# STM32_microcontroller_power.net
KiCad netlist of a schematic drawn in Altium Designer
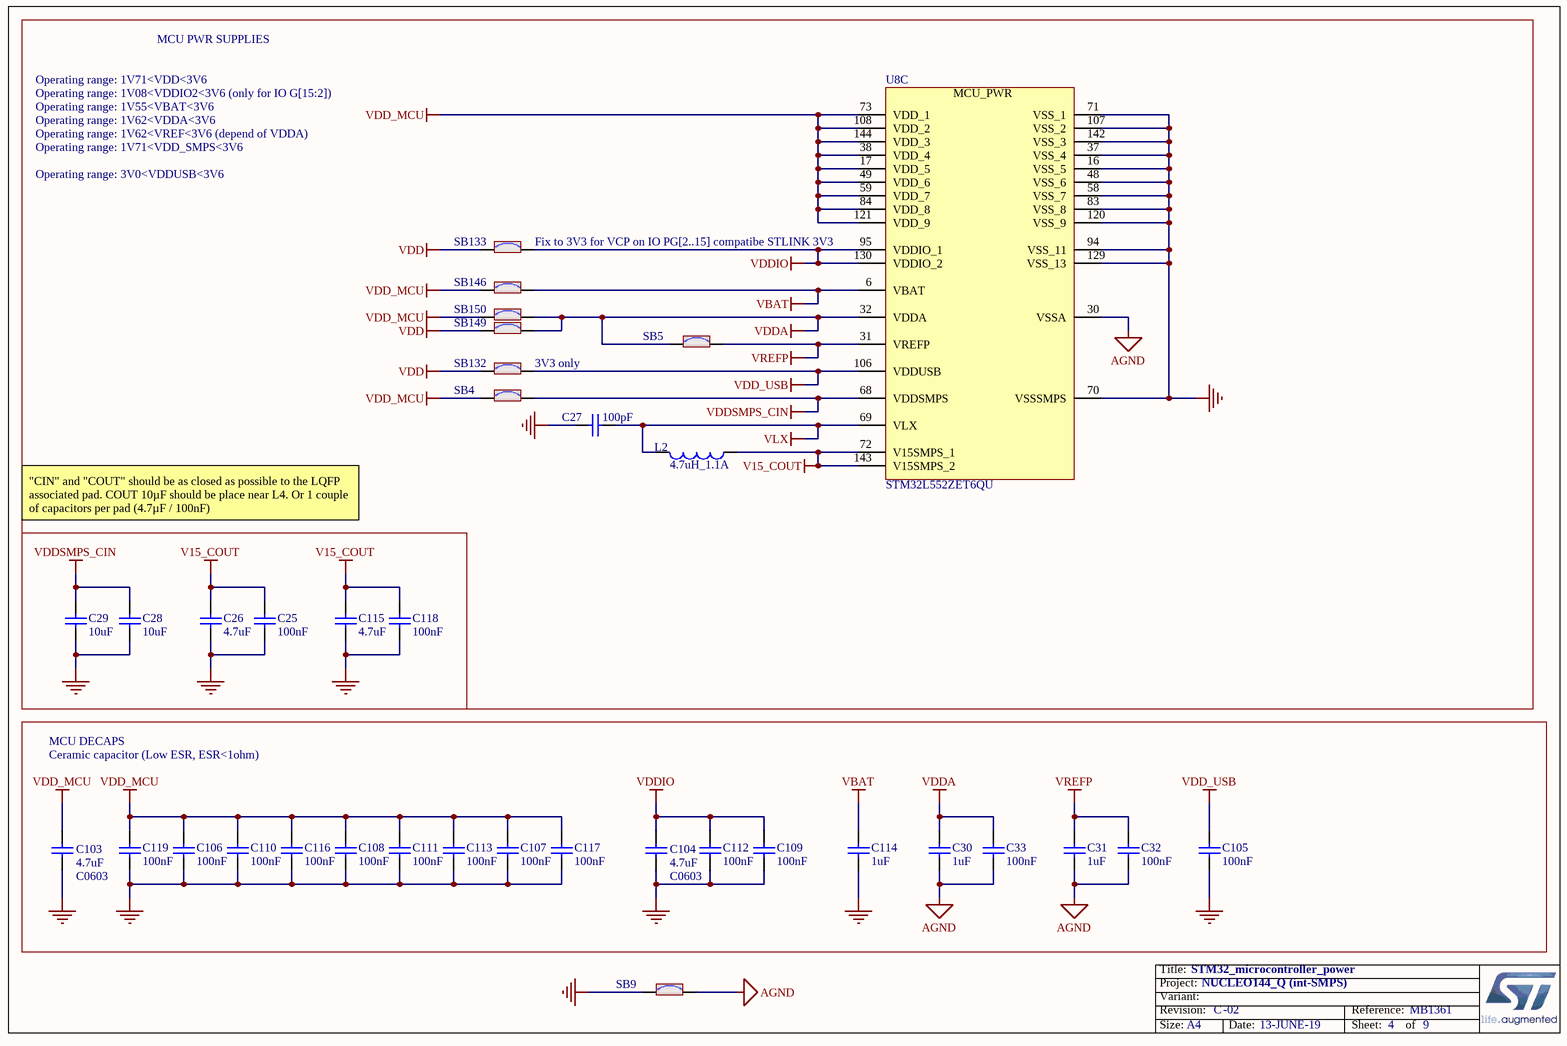
[diagram p0: STM32_microcontroller_power.SchDoc]

(export (version "E")
  (design (tool "Eeschema 10.0.6"))
  (components
    (comp (ref "C25")
      (value "100nF")
      (footprint "C0402")
      (description "Capacitor, MLCC, 100nF, 16V, X7R, 10%, 0402, T=0,5mm")
      (fields
        (field (name "INTERNAL_PART_NUMBER") "MCD-00102")
        (field (name "MANUFACTURER_PART_NUMBER") "CC0402KRX7R7BB104")
        (field (name "PROVIDED_BY") "SUBCO")
      )
      (libsource (lib "MCD_PARTS_database") (part "Capacitor"))
    )
    (comp (ref "C26")
      (value "4.7uF")
      (footprint "C0402")
      (description "Capacitor, MLCC, 4.7uF, 6V3, X5R, 20%, 0402, T=0,5mm")
      (fields
        (field (name "INTERNAL_PART_NUMBER") "MCD-01356")
        (field (name "MANUFACTURER_PART_NUMBER") "GRM155R60J475ME47")
        (field (name "PROVIDED_BY") "Subcon")
      )
      (libsource (lib "MCD_PARTS_database") (part "Capacitor"))
    )
    (comp (ref "C27")
      (value "100pF")
      (footprint "C0402")
      (description "Capacitor, MLCC, 100pF, 50V, NPO, 5%, 0402, T=0,5mm")
      (fields
        (field (name "INTERNAL_PART_NUMBER") "MCD-00205")
        (field (name "MANUFACTURER_PART_NUMBER") "CC0402JRNPO9BN101")
        (field (name "PROVIDED_BY") "Subcon")
      )
      (libsource (lib "MCD_PARTS_database") (part "Capacitor"))
    )
    (comp (ref "C28")
      (value "10uF")
      (footprint "C0402")
      (description "Capacitor, MLCC, 10uF, 4V, X5R, 20%, 0402, T=0,5mm")
      (fields
        (field (name "INTERNAL_PART_NUMBER") "MCD-01355")
        (field (name "MANUFACTURER_PART_NUMBER") "GRM155R60G106ME44")
        (field (name "PROVIDED_BY") "Subcon")
      )
      (libsource (lib "MCD_PARTS_database") (part "Capacitor"))
    )
    (comp (ref "C29")
      (value "10uF")
      (footprint "C0402")
      (description "Capacitor, MLCC, 10uF, 4V, X5R, 20%, 0402, T=0,5mm")
      (fields
        (field (name "INTERNAL_PART_NUMBER") "MCD-01355")
        (field (name "MANUFACTURER_PART_NUMBER") "GRM155R60G106ME44")
        (field (name "PROVIDED_BY") "Subcon")
      )
      (libsource (lib "MCD_PARTS_database") (part "Capacitor"))
    )
    (comp (ref "C30")
      (value "1uF")
      (footprint "C0603")
      (description "Capacitor, MLCC, 1uF, 16V, X5R, 10%, 0603, T=0,8mm")
      (fields
        (field (name "INTERNAL_PART_NUMBER") "MCD-00010")
        (field (name "MANUFACTURER_PART_NUMBER") "CC0603KRX5R7BB105")
        (field (name "PROVIDED_BY") "SUBCO")
      )
      (libsource (lib "MCD_PARTS_database") (part "Capacitor"))
    )
    (comp (ref "C31")
      (value "1uF")
      (footprint "C0603")
      (description "Capacitor, MLCC, 1uF, 16V, X5R, 10%, 0603, T=0,8mm")
      (fields
        (field (name "INTERNAL_PART_NUMBER") "MCD-00010")
        (field (name "MANUFACTURER_PART_NUMBER") "CC0603KRX5R7BB105")
        (field (name "PROVIDED_BY") "SUBCO")
      )
      (libsource (lib "MCD_PARTS_database") (part "Capacitor"))
    )
    (comp (ref "C32")
      (value "100nF")
      (footprint "C0402")
      (description "Capacitor, MLCC, 100nF, 16V, X7R, 10%, 0402, T=0,5mm")
      (fields
        (field (name "INTERNAL_PART_NUMBER") "MCD-00102")
        (field (name "MANUFACTURER_PART_NUMBER") "CC0402KRX7R7BB104")
        (field (name "PROVIDED_BY") "SUBCO")
      )
      (libsource (lib "MCD_PARTS_database") (part "Capacitor"))
    )
    (comp (ref "C33")
      (value "100nF")
      (footprint "C0402")
      (description "Capacitor, MLCC, 100nF, 16V, X7R, 10%, 0402, T=0,5mm")
      (fields
        (field (name "INTERNAL_PART_NUMBER") "MCD-00102")
        (field (name "MANUFACTURER_PART_NUMBER") "CC0402KRX7R7BB104")
        (field (name "PROVIDED_BY") "SUBCO")
      )
      (libsource (lib "MCD_PARTS_database") (part "Capacitor"))
    )
    (comp (ref "C103")
      (value "4.7uF")
      (footprint "C0603")
      (description "Capacitor, MLCC, 4.7µF, 10V, X5R, 20%, 0603, T=0,8mm")
      (fields
        (field (name "INTERNAL_PART_NUMBER") "MCD-01121")
        (field (name "MANUFACTURER_PART_NUMBER") "GRM188R61A475ME15")
        (field (name "PACKAGE") "C0603")
        (field (name "PROVIDED_BY") "Subcon")
      )
      (libsource (lib "MCD_PARTS_database") (part "Capacitor"))
    )
    (comp (ref "C104")
      (value "4.7uF")
      (footprint "C0603")
      (description "Capacitor, MLCC, 4.7µF, 10V, X5R, 20%, 0603, T=0,8mm")
      (fields
        (field (name "INTERNAL_PART_NUMBER") "MCD-01121")
        (field (name "MANUFACTURER_PART_NUMBER") "GRM188R61A475ME15")
        (field (name "PACKAGE") "C0603")
        (field (name "PROVIDED_BY") "Subcon")
      )
      (libsource (lib "MCD_PARTS_database") (part "Capacitor"))
    )
    (comp (ref "C105")
      (value "100nF")
      (footprint "C0402")
      (description "Capacitor, MLCC, 100nF, 16V, X7R, 10%, 0402, T=0,5mm")
      (fields
        (field (name "INTERNAL_PART_NUMBER") "MCD-00102")
        (field (name "MANUFACTURER_PART_NUMBER") "CC0402KRX7R7BB104")
        (field (name "PROVIDED_BY") "SUBCO")
      )
      (libsource (lib "MCD_PARTS_database") (part "Capacitor"))
    )
    (comp (ref "C106")
      (value "100nF")
      (footprint "C0402")
      (description "Capacitor, MLCC, 100nF, 16V, X7R, 10%, 0402, T=0,5mm")
      (fields
        (field (name "INTERNAL_PART_NUMBER") "MCD-00102")
        (field (name "MANUFACTURER_PART_NUMBER") "CC0402KRX7R7BB104")
        (field (name "PROVIDED_BY") "SUBCO")
      )
      (libsource (lib "MCD_PARTS_database") (part "Capacitor"))
    )
    (comp (ref "C107")
      (value "100nF")
      (footprint "C0402")
      (description "Capacitor, MLCC, 100nF, 16V, X7R, 10%, 0402, T=0,5mm")
      (fields
        (field (name "INTERNAL_PART_NUMBER") "MCD-00102")
        (field (name "MANUFACTURER_PART_NUMBER") "CC0402KRX7R7BB104")
        (field (name "PROVIDED_BY") "SUBCO")
      )
      (libsource (lib "MCD_PARTS_database") (part "Capacitor"))
    )
    (comp (ref "C108")
      (value "100nF")
      (footprint "C0402")
      (description "Capacitor, MLCC, 100nF, 16V, X7R, 10%, 0402, T=0,5mm")
      (fields
        (field (name "INTERNAL_PART_NUMBER") "MCD-00102")
        (field (name "MANUFACTURER_PART_NUMBER") "CC0402KRX7R7BB104")
        (field (name "PROVIDED_BY") "SUBCO")
      )
      (libsource (lib "MCD_PARTS_database") (part "Capacitor"))
    )
    (comp (ref "C109")
      (value "100nF")
      (footprint "C0402")
      (description "Capacitor, MLCC, 100nF, 16V, X7R, 10%, 0402, T=0,5mm")
      (fields
        (field (name "INTERNAL_PART_NUMBER") "MCD-00102")
        (field (name "MANUFACTURER_PART_NUMBER") "CC0402KRX7R7BB104")
        (field (name "PROVIDED_BY") "SUBCO")
      )
      (libsource (lib "MCD_PARTS_database") (part "Capacitor"))
    )
    (comp (ref "C110")
      (value "100nF")
      (footprint "C0402")
      (description "Capacitor, MLCC, 100nF, 16V, X7R, 10%, 0402, T=0,5mm")
      (fields
        (field (name "INTERNAL_PART_NUMBER") "MCD-00102")
        (field (name "MANUFACTURER_PART_NUMBER") "CC0402KRX7R7BB104")
        (field (name "PROVIDED_BY") "SUBCO")
      )
      (libsource (lib "MCD_PARTS_database") (part "Capacitor"))
    )
    (comp (ref "C111")
      (value "100nF")
      (footprint "C0402")
      (description "Capacitor, MLCC, 100nF, 16V, X7R, 10%, 0402, T=0,5mm")
      (fields
        (field (name "INTERNAL_PART_NUMBER") "MCD-00102")
        (field (name "MANUFACTURER_PART_NUMBER") "CC0402KRX7R7BB104")
        (field (name "PROVIDED_BY") "SUBCO")
      )
      (libsource (lib "MCD_PARTS_database") (part "Capacitor"))
    )
    (comp (ref "C112")
      (value "100nF")
      (footprint "C0402")
      (description "Capacitor, MLCC, 100nF, 16V, X7R, 10%, 0402, T=0,5mm")
      (fields
        (field (name "INTERNAL_PART_NUMBER") "MCD-00102")
        (field (name "MANUFACTURER_PART_NUMBER") "CC0402KRX7R7BB104")
        (field (name "PROVIDED_BY") "SUBCO")
      )
      (libsource (lib "MCD_PARTS_database") (part "Capacitor"))
    )
    (comp (ref "C113")
      (value "100nF")
      (footprint "C0402")
      (description "Capacitor, MLCC, 100nF, 16V, X7R, 10%, 0402, T=0,5mm")
      (fields
        (field (name "INTERNAL_PART_NUMBER") "MCD-00102")
        (field (name "MANUFACTURER_PART_NUMBER") "CC0402KRX7R7BB104")
        (field (name "PROVIDED_BY") "SUBCO")
      )
      (libsource (lib "MCD_PARTS_database") (part "Capacitor"))
    )
    (comp (ref "C114")
      (value "1uF")
      (footprint "C0603")
      (description "Capacitor, MLCC, 1uF, 16V, X5R, 10%, 0603, T=0,8mm")
      (fields
        (field (name "INTERNAL_PART_NUMBER") "MCD-00010")
        (field (name "MANUFACTURER_PART_NUMBER") "CC0603KRX5R7BB105")
        (field (name "PROVIDED_BY") "SUBCO")
      )
      (libsource (lib "MCD_PARTS_database") (part "Capacitor"))
    )
    (comp (ref "C115")
      (value "4.7uF")
      (footprint "C0402")
      (description "Capacitor, MLCC, 4.7uF, 6V3, X5R, 20%, 0402, T=0,5mm")
      (fields
        (field (name "INTERNAL_PART_NUMBER") "MCD-01356")
        (field (name "MANUFACTURER_PART_NUMBER") "GRM155R60J475ME47")
        (field (name "PROVIDED_BY") "Subcon")
      )
      (libsource (lib "MCD_PARTS_database") (part "Capacitor"))
    )
    (comp (ref "C116")
      (value "100nF")
      (footprint "C0402")
      (description "Capacitor, MLCC, 100nF, 16V, X7R, 10%, 0402, T=0,5mm")
      (fields
        (field (name "INTERNAL_PART_NUMBER") "MCD-00102")
        (field (name "MANUFACTURER_PART_NUMBER") "CC0402KRX7R7BB104")
        (field (name "PROVIDED_BY") "SUBCO")
      )
      (libsource (lib "MCD_PARTS_database") (part "Capacitor"))
    )
    (comp (ref "C117")
      (value "100nF")
      (footprint "C0402")
      (description "Capacitor, MLCC, 100nF, 16V, X7R, 10%, 0402, T=0,5mm")
      (fields
        (field (name "INTERNAL_PART_NUMBER") "MCD-00102")
        (field (name "MANUFACTURER_PART_NUMBER") "CC0402KRX7R7BB104")
        (field (name "PROVIDED_BY") "SUBCO")
      )
      (libsource (lib "MCD_PARTS_database") (part "Capacitor"))
    )
    (comp (ref "C118")
      (value "100nF")
      (footprint "C0402")
      (description "Capacitor, MLCC, 100nF, 16V, X7R, 10%, 0402, T=0,5mm")
      (fields
        (field (name "INTERNAL_PART_NUMBER") "MCD-00102")
        (field (name "MANUFACTURER_PART_NUMBER") "CC0402KRX7R7BB104")
        (field (name "PROVIDED_BY") "SUBCO")
      )
      (libsource (lib "MCD_PARTS_database") (part "Capacitor"))
    )
    (comp (ref "C119")
      (value "100nF")
      (footprint "C0402")
      (description "Capacitor, MLCC, 100nF, 16V, X7R, 10%, 0402, T=0,5mm")
      (fields
        (field (name "INTERNAL_PART_NUMBER") "MCD-00102")
        (field (name "MANUFACTURER_PART_NUMBER") "CC0402KRX7R7BB104")
        (field (name "PROVIDED_BY") "SUBCO")
      )
      (libsource (lib "MCD_PARTS_database") (part "Capacitor"))
    )
    (comp (ref "L2")
      (value "4.7uH_1.1A")
      (footprint "IND_TDK_MLP2016H4R7MT0S1")
      (description "Power Inductor 4.7uH 1.1A 160 mOHM 20% SMD Multilayer ferrite.")
      (fields
        (field (name "INTERNAL_PART_NUMBER") "MCD-01786")
        (field (name "MANUFACTURER_PART_NUMBER") "MLP2016H4R7MT0S1")
        (field (name "PROVIDED_BY") "SUBCO")
      )
      (libsource (lib "MCD_PARTS_database") (part "Inductor"))
    )
    (comp (ref "SB4")
      (value "~")
      (footprint "SOLDER-BRIDGE_R0603-0R")
      (description "Solder Bridge ON")
      (fields (field (name "INTERNAL_PART_NUMBER") "MCD-00071") (field (name "PROVIDED_BY") "Subcon"))
      (libsource (lib "MCD_PARTS_database") (part "SB_ON"))
    )
    (comp (ref "SB5")
      (value "~")
      (footprint "SOLDER-BRIDGE_R0603-0R")
      (description "Solder Bridge ON")
      (fields (field (name "INTERNAL_PART_NUMBER") "MCD-00071") (field (name "PROVIDED_BY") "Subcon"))
      (libsource (lib "MCD_PARTS_database") (part "SB_ON"))
    )
    (comp (ref "SB9")
      (value "~")
      (footprint "SOLDER-BRIDGE_R0603-0R")
      (description "Solder Bridge ON")
      (fields (field (name "INTERNAL_PART_NUMBER") "MCD-00071") (field (name "PROVIDED_BY") "Subcon"))
      (libsource (lib "MCD_PARTS_database") (part "SB_ON"))
    )
    (comp (ref "SB132")
      (value "~")
      (footprint "SOLDER-BRIDGE_R0603-0R")
      (description "Solder Bridge ON")
      (fields (field (name "INTERNAL_PART_NUMBER") "MCD-00071") (field (name "PROVIDED_BY") "Subcon"))
      (libsource (lib "MCD_PARTS_database") (part "SB_ON"))
    )
    (comp (ref "SB133")
      (value "~")
      (footprint "SOLDER-BRIDGE_R0603-0R")
      (description "Solder Bridge ON")
      (fields (field (name "INTERNAL_PART_NUMBER") "MCD-00071") (field (name "PROVIDED_BY") "Subcon"))
      (libsource (lib "MCD_PARTS_database") (part "SB_ON"))
    )
    (comp (ref "SB146")
      (value "~")
      (footprint "SOLDER-BRIDGE_R0603-0R")
      (description "Solder Bridge ON")
      (fields (field (name "INTERNAL_PART_NUMBER") "MCD-00071") (field (name "PROVIDED_BY") "Subcon"))
      (libsource (lib "MCD_PARTS_database") (part "SB_ON"))
    )
    (comp (ref "SB149")
      (value "~")
      (footprint "SOLDER-BRIDGE_R0603-0R")
      (description "Solder Bridge ON")
      (fields (field (name "INTERNAL_PART_NUMBER") "MCD-00071") (field (name "PROVIDED_BY") "Subcon"))
      (libsource (lib "MCD_PARTS_database") (part "SB_ON"))
    )
    (comp (ref "SB150")
      (value "~")
      (footprint "SOLDER-BRIDGE_R0603-0R")
      (description "Solder Bridge ON")
      (fields (field (name "INTERNAL_PART_NUMBER") "MCD-00071") (field (name "PROVIDED_BY") "Subcon"))
      (libsource (lib "MCD_PARTS_database") (part "SB_ON"))
    )
    (comp (ref "U8")
      (value "STM32L552ZET6QU")
      (footprint "ICC_LQFP144_20X20_P050")
      (description "STM32L552ZET6Q MCU,LQFP144 20x20, 0.5, no AES, Q for Int SMPS")
      (fields
        (field (name "INTERNAL_PART_NUMBER") "MCD-01055")
        (field (name "MANUFACTURER") "STMICROELECTRONICS")
        (field (name "PROVIDED_BY") "SUBCO with ST control")
      )
      (libsource (lib "MCD_PARTS_database") (part "STM32L552ZET6QU"))
    )
  )
  (nets
    (net (code "1") (name "AGND") (class "Default")
      (node (ref "C30") (pin "2") (pinfunction "2_2") (pintype "passive"))
      (node (ref "C31") (pin "2") (pinfunction "2_2") (pintype "passive"))
      (node (ref "C32") (pin "1") (pinfunction "1_1") (pintype "passive"))
      (node (ref "C33") (pin "1") (pinfunction "1_1") (pintype "passive"))
      (node (ref "SB9") (pin "2") (pinfunction "2_2") (pintype "passive"))
      (node (ref "U8") (pin "30") (pinfunction "VSSA_30") (pintype "passive"))
    )
    (net (code "2") (name "GND") (class "Default")
      (node (ref "C103") (pin "1") (pinfunction "1_1") (pintype "passive"))
      (node (ref "C104") (pin "1") (pinfunction "1_1") (pintype "passive"))
      (node (ref "C105") (pin "1") (pinfunction "1_1") (pintype "passive"))
      (node (ref "C106") (pin "1") (pinfunction "1_1") (pintype "passive"))
      (node (ref "C107") (pin "1") (pinfunction "1_1") (pintype "passive"))
      (node (ref "C108") (pin "1") (pinfunction "1_1") (pintype "passive"))
      (node (ref "C109") (pin "1") (pinfunction "1_1") (pintype "passive"))
      (node (ref "C110") (pin "1") (pinfunction "1_1") (pintype "passive"))
      (node (ref "C111") (pin "1") (pinfunction "1_1") (pintype "passive"))
      (node (ref "C112") (pin "1") (pinfunction "1_1") (pintype "passive"))
      (node (ref "C113") (pin "1") (pinfunction "1_1") (pintype "passive"))
      (node (ref "C114") (pin "1") (pinfunction "1_1") (pintype "passive"))
      (node (ref "C115") (pin "1") (pinfunction "1_1") (pintype "passive"))
      (node (ref "C116") (pin "1") (pinfunction "1_1") (pintype "passive"))
      (node (ref "C117") (pin "1") (pinfunction "1_1") (pintype "passive"))
      (node (ref "C118") (pin "1") (pinfunction "1_1") (pintype "passive"))
      (node (ref "C119") (pin "1") (pinfunction "1_1") (pintype "passive"))
      (node (ref "C25") (pin "1") (pinfunction "1_1") (pintype "passive"))
      (node (ref "C26") (pin "1") (pinfunction "1_1") (pintype "passive"))
      (node (ref "C27") (pin "1") (pinfunction "1_1") (pintype "passive"))
      (node (ref "C28") (pin "1") (pinfunction "1_1") (pintype "passive"))
      (node (ref "C29") (pin "1") (pinfunction "1_1") (pintype "passive"))
      (node (ref "SB9") (pin "1") (pinfunction "1_1") (pintype "passive"))
      (node (ref "U8") (pin "107") (pinfunction "VSS_2_107") (pintype "passive"))
      (node (ref "U8") (pin "120") (pinfunction "VSS_9_120") (pintype "passive"))
      (node (ref "U8") (pin "129") (pinfunction "VSS_13_129") (pintype "passive"))
      (node (ref "U8") (pin "142") (pinfunction "VSS_3_142") (pintype "passive"))
      (node (ref "U8") (pin "16") (pinfunction "VSS_5_16") (pintype "passive"))
      (node (ref "U8") (pin "37") (pinfunction "VSS_4_37") (pintype "passive"))
      (node (ref "U8") (pin "48") (pinfunction "VSS_6_48") (pintype "passive"))
      (node (ref "U8") (pin "58") (pinfunction "VSS_7_58") (pintype "passive"))
      (node (ref "U8") (pin "70") (pinfunction "VSSSMPS_70") (pintype "passive"))
      (node (ref "U8") (pin "71") (pinfunction "VSS_1_71") (pintype "passive"))
      (node (ref "U8") (pin "83") (pinfunction "VSS_8_83") (pintype "passive"))
      (node (ref "U8") (pin "94") (pinfunction "VSS_11_94") (pintype "passive"))
    )
    (net (code "3") (name "V15_COUT") (class "Default")
      (node (ref "C115") (pin "2") (pinfunction "2_2") (pintype "passive"))
      (node (ref "C118") (pin "2") (pinfunction "2_2") (pintype "passive"))
      (node (ref "C25") (pin "2") (pinfunction "2_2") (pintype "passive"))
      (node (ref "C26") (pin "2") (pinfunction "2_2") (pintype "passive"))
      (node (ref "L2") (pin "1") (pinfunction "1_1") (pintype "passive"))
      (node (ref "U8") (pin "143") (pinfunction "V15SMPS_2_143") (pintype "passive"))
      (node (ref "U8") (pin "72") (pinfunction "V15SMPS_1_72") (pintype "passive"))
    )
    (net (code "4") (name "VBAT") (class "Default")
      (node (ref "C114") (pin "2") (pinfunction "2_2") (pintype "passive"))
      (node (ref "SB146") (pin "2") (pinfunction "2_2") (pintype "passive"))
      (node (ref "U8") (pin "6") (pinfunction "VBAT_6") (pintype "passive"))
    )
    (net (code "5") (name "VDD") (class "Default")
      (node (ref "SB132") (pin "1") (pinfunction "1_1") (pintype "passive"))
      (node (ref "SB133") (pin "1") (pinfunction "1_1") (pintype "passive"))
      (node (ref "SB149") (pin "1") (pinfunction "1_1") (pintype "passive"))
    )
    (net (code "6") (name "VDDA") (class "Default")
      (node (ref "C30") (pin "1") (pinfunction "1_1") (pintype "passive"))
      (node (ref "C33") (pin "2") (pinfunction "2_2") (pintype "passive"))
      (node (ref "SB149") (pin "2") (pinfunction "2_2") (pintype "passive"))
      (node (ref "SB150") (pin "2") (pinfunction "2_2") (pintype "passive"))
      (node (ref "SB5") (pin "1") (pinfunction "1_1") (pintype "passive"))
      (node (ref "U8") (pin "32") (pinfunction "VDDA_32") (pintype "passive"))
    )
    (net (code "7") (name "VDDIO") (class "Default")
      (node (ref "C104") (pin "2") (pinfunction "2_2") (pintype "passive"))
      (node (ref "C109") (pin "2") (pinfunction "2_2") (pintype "passive"))
      (node (ref "C112") (pin "2") (pinfunction "2_2") (pintype "passive"))
      (node (ref "SB133") (pin "2") (pinfunction "2_2") (pintype "passive"))
      (node (ref "U8") (pin "130") (pinfunction "VDDIO_2_130") (pintype "passive"))
      (node (ref "U8") (pin "95") (pinfunction "VDDIO_1_95") (pintype "passive"))
    )
    (net (code "8") (name "VDDSMPS_CIN") (class "Default")
      (node (ref "C28") (pin "2") (pinfunction "2_2") (pintype "passive"))
      (node (ref "C29") (pin "2") (pinfunction "2_2") (pintype "passive"))
      (node (ref "SB4") (pin "2") (pinfunction "2_2") (pintype "passive"))
      (node (ref "U8") (pin "68") (pinfunction "VDDSMPS_68") (pintype "passive"))
    )
    (net (code "9") (name "VDD_MCU") (class "Default")
      (node (ref "C103") (pin "2") (pinfunction "2_2") (pintype "passive"))
      (node (ref "C106") (pin "2") (pinfunction "2_2") (pintype "passive"))
      (node (ref "C107") (pin "2") (pinfunction "2_2") (pintype "passive"))
      (node (ref "C108") (pin "2") (pinfunction "2_2") (pintype "passive"))
      (node (ref "C110") (pin "2") (pinfunction "2_2") (pintype "passive"))
      (node (ref "C111") (pin "2") (pinfunction "2_2") (pintype "passive"))
      (node (ref "C113") (pin "2") (pinfunction "2_2") (pintype "passive"))
      (node (ref "C116") (pin "2") (pinfunction "2_2") (pintype "passive"))
      (node (ref "C117") (pin "2") (pinfunction "2_2") (pintype "passive"))
      (node (ref "C119") (pin "2") (pinfunction "2_2") (pintype "passive"))
      (node (ref "SB146") (pin "1") (pinfunction "1_1") (pintype "passive"))
      (node (ref "SB150") (pin "1") (pinfunction "1_1") (pintype "passive"))
      (node (ref "SB4") (pin "1") (pinfunction "1_1") (pintype "passive"))
      (node (ref "U8") (pin "108") (pinfunction "VDD_2_108") (pintype "passive"))
      (node (ref "U8") (pin "121") (pinfunction "VDD_9_121") (pintype "passive"))
      (node (ref "U8") (pin "144") (pinfunction "VDD_3_144") (pintype "passive"))
      (node (ref "U8") (pin "17") (pinfunction "VDD_5_17") (pintype "passive"))
      (node (ref "U8") (pin "38") (pinfunction "VDD_4_38") (pintype "passive"))
      (node (ref "U8") (pin "49") (pinfunction "VDD_6_49") (pintype "passive"))
      (node (ref "U8") (pin "59") (pinfunction "VDD_7_59") (pintype "passive"))
      (node (ref "U8") (pin "73") (pinfunction "VDD_1_73") (pintype "passive"))
      (node (ref "U8") (pin "84") (pinfunction "VDD_8_84") (pintype "passive"))
    )
    (net (code "10") (name "VDD_USB") (class "Default")
      (node (ref "C105") (pin "2") (pinfunction "2_2") (pintype "passive"))
      (node (ref "SB132") (pin "2") (pinfunction "2_2") (pintype "passive"))
      (node (ref "U8") (pin "106") (pinfunction "VDDUSB_106") (pintype "passive"))
    )
    (net (code "11") (name "VLX") (class "Default")
      (node (ref "C27") (pin "2") (pinfunction "2_2") (pintype "passive"))
      (node (ref "L2") (pin "2") (pinfunction "2_2") (pintype "passive"))
      (node (ref "U8") (pin "69") (pinfunction "VLX_69") (pintype "passive"))
    )
    (net (code "12") (name "VREFP") (class "Default")
      (node (ref "C31") (pin "1") (pinfunction "1_1") (pintype "passive"))
      (node (ref "C32") (pin "2") (pinfunction "2_2") (pintype "passive"))
      (node (ref "SB5") (pin "2") (pinfunction "2_2") (pintype "passive"))
      (node (ref "U8") (pin "31") (pinfunction "VREFP_31") (pintype "passive"))
    )
  )
)
